# quadbase_ble113.net
KiCad netlist of a schematic drawn in EAGLE
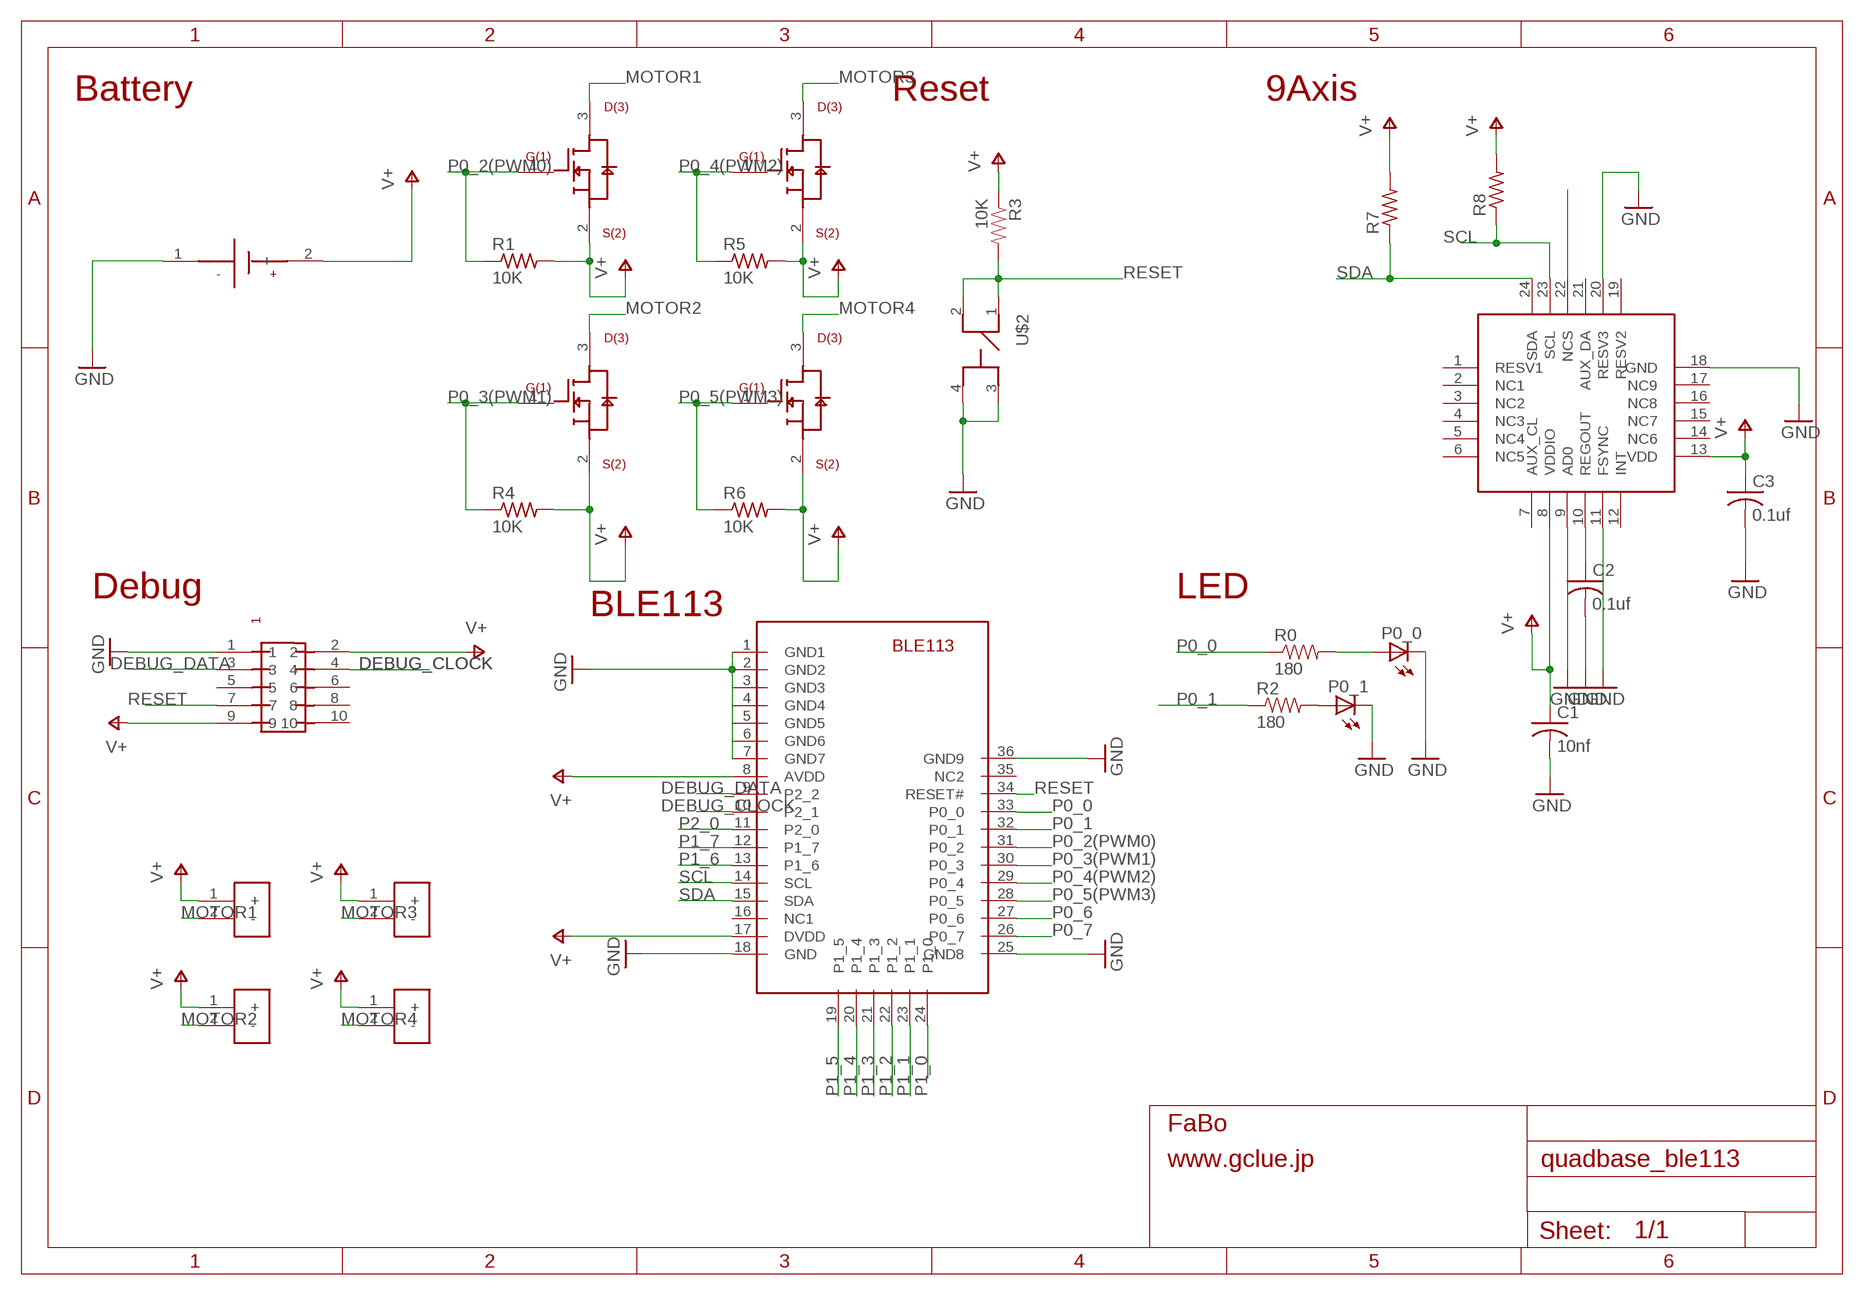
[diagram p0: schematic, sheet 1]

(export (version "E")
  (design (tool "Eeschema 10.0.6"))
  (components
    (comp (ref "C1")
      (value "10nf")
      (footprint "eagle-import:C0603")
      (libsource (lib "eagle-import") (part "C-USC0603"))
    )
    (comp (ref "C2")
      (value "0.1uf")
      (footprint "eagle-import:C0603")
      (libsource (lib "eagle-import") (part "C-USC0603"))
    )
    (comp (ref "C3")
      (value "0.1uf")
      (footprint "eagle-import:C0603")
      (libsource (lib "eagle-import") (part "C-USC0603"))
    )
    (comp (ref "MOTOR1")
      (value "SMD-MOTOR")
      (footprint "eagle-import:SMD-MOTOR")
      (libsource (lib "eagle-import") (part "SMD-MOTOR"))
    )
    (comp (ref "MOTOR2")
      (value "SMD-MOTOR")
      (footprint "eagle-import:SMD-MOTOR")
      (libsource (lib "eagle-import") (part "SMD-MOTOR"))
    )
    (comp (ref "MOTOR3")
      (value "SMD-MOTOR")
      (footprint "eagle-import:SMD-MOTOR")
      (libsource (lib "eagle-import") (part "SMD-MOTOR"))
    )
    (comp (ref "MOTOR4")
      (value "SMD-MOTOR")
      (footprint "eagle-import:SMD-MOTOR")
      (libsource (lib "eagle-import") (part "SMD-MOTOR"))
    )
    (comp (ref "P0_0")
      (value "LEDCHIP-LED0603")
      (footprint "eagle-import:CHIP-LED0603")
      (libsource (lib "eagle-import") (part "LEDCHIP-LED0603"))
    )
    (comp (ref "P0_1")
      (value "LEDCHIP-LED0603")
      (footprint "eagle-import:CHIP-LED0603")
      (libsource (lib "eagle-import") (part "LEDCHIP-LED0603"))
    )
    (comp (ref "R0")
      (value "180")
      (footprint "eagle-import:0603-RES")
      (libsource (lib "eagle-import") (part "RESISTOR0603-RES"))
    )
    (comp (ref "R1")
      (value "10K")
      (footprint "eagle-import:R0603")
      (libsource (lib "eagle-import") (part "R-US_R0603"))
    )
    (comp (ref "R2")
      (value "180")
      (footprint "eagle-import:0603-RES")
      (libsource (lib "eagle-import") (part "RESISTOR0603-RES"))
    )
    (comp (ref "R3")
      (value "10K")
      (footprint "eagle-import:0603-RES")
      (libsource (lib "eagle-import") (part "RESISTOR0603-RES"))
    )
    (comp (ref "R4")
      (value "10K")
      (footprint "eagle-import:R0603")
      (libsource (lib "eagle-import") (part "R-US_R0603"))
    )
    (comp (ref "R5")
      (value "10K")
      (footprint "eagle-import:R0603")
      (libsource (lib "eagle-import") (part "R-US_R0603"))
    )
    (comp (ref "R6")
      (value "10K")
      (footprint "eagle-import:R0603")
      (libsource (lib "eagle-import") (part "R-US_R0603"))
    )
    (comp (ref "R7")
      (value "R-US_R0603")
      (footprint "eagle-import:R0603")
      (libsource (lib "eagle-import") (part "R-US_R0603"))
    )
    (comp (ref "R8")
      (value "R-US_R0603")
      (footprint "eagle-import:R0603")
      (libsource (lib "eagle-import") (part "R-US_R0603"))
    )
    (comp (ref "U$1")
      (value "SMD-SUPPLY")
      (footprint "eagle-import:SMD_SUPPLY")
      (libsource (lib "eagle-import") (part "SMD-SUPPLY"))
    )
    (comp (ref "U$2")
      (value "SWITCH-LS6J2M-T")
      (footprint "eagle-import:SWITCH-LS6J2M-T")
      (libsource (lib "eagle-import") (part "SWITCH-LS6J2M-T"))
    )
    (comp (ref "U$3")
      (value "PIN-HEADER-SMT(1.27MM)2X5")
      (footprint "eagle-import:PIN-HEADER-SMT(1.27MM)2X5")
      (libsource (lib "eagle-import") (part "PIN-HEADER-SMT(1.27MM)2X5"))
    )
    (comp (ref "U$4")
      (value "BLE113")
      (footprint "eagle-import:BLE113")
      (libsource (lib "eagle-import") (part "BLE113"))
    )
    (comp (ref "U$5")
      (value "VISHAY-SI2318CDS")
      (footprint "eagle-import:VISHAY-SI2318CDS")
      (libsource (lib "eagle-import") (part "VISHAY-SI2318CDS"))
    )
    (comp (ref "U$7")
      (value "VISHAY-SI2318CDS")
      (footprint "eagle-import:VISHAY-SI2318CDS")
      (libsource (lib "eagle-import") (part "VISHAY-SI2318CDS"))
    )
    (comp (ref "U$8")
      (value "VISHAY-SI2318CDS")
      (footprint "eagle-import:VISHAY-SI2318CDS")
      (libsource (lib "eagle-import") (part "VISHAY-SI2318CDS"))
    )
    (comp (ref "U$9")
      (value "VISHAY-SI2318CDS")
      (footprint "eagle-import:VISHAY-SI2318CDS")
      (libsource (lib "eagle-import") (part "VISHAY-SI2318CDS"))
    )
    (comp (ref "U$10")
      (value "INVENSENSE-MPU9250")
      (footprint "eagle-import:INVENSENSE-MPU9250")
      (libsource (lib "eagle-import") (part "INVENSENSE-MPU9250"))
    )
  )
  (nets
    (net (code "1") (name "/DEBUG_CLOCK") (class "Default")
      (node (ref "U$3") (pin "4") (pinfunction "4_4") (pintype "bidirectional"))
      (node (ref "U$4") (pin "10") (pinfunction "P2_1_10") (pintype "bidirectional"))
    )
    (net (code "2") (name "/DEBUG_DATA") (class "Default")
      (node (ref "U$3") (pin "3") (pinfunction "3_3") (pintype "bidirectional"))
      (node (ref "U$4") (pin "9") (pinfunction "P2_2_9") (pintype "bidirectional"))
    )
    (net (code "3") (name "/MOTOR1") (class "Default")
      (node (ref "MOTOR1") (pin "2") (pinfunction "-_2") (pintype "bidirectional"))
      (node (ref "U$5") (pin "3") (pinfunction "P$3_3") (pintype "bidirectional"))
    )
    (net (code "4") (name "/MOTOR2") (class "Default")
      (node (ref "MOTOR2") (pin "2") (pinfunction "-_2") (pintype "bidirectional"))
      (node (ref "U$7") (pin "3") (pinfunction "P$3_3") (pintype "bidirectional"))
    )
    (net (code "5") (name "/MOTOR3") (class "Default")
      (node (ref "MOTOR3") (pin "2") (pinfunction "-_2") (pintype "bidirectional"))
      (node (ref "U$8") (pin "3") (pinfunction "P$3_3") (pintype "bidirectional"))
    )
    (net (code "6") (name "/MOTOR4") (class "Default")
      (node (ref "MOTOR4") (pin "2") (pinfunction "-_2") (pintype "bidirectional"))
      (node (ref "U$9") (pin "3") (pinfunction "P$3_3") (pintype "bidirectional"))
    )
    (net (code "7") (name "/P0_0") (class "Default")
      (node (ref "R0") (pin "1") (pinfunction "1_1") (pintype "passive"))
      (node (ref "U$4") (pin "33") (pinfunction "P0_0_33") (pintype "bidirectional"))
    )
    (net (code "8") (name "/P0_1") (class "Default")
      (node (ref "R2") (pin "1") (pinfunction "1_1") (pintype "passive"))
      (node (ref "U$4") (pin "32") (pinfunction "P0_1_32") (pintype "bidirectional"))
    )
    (net (code "9") (name "/P0_2(PWM0)") (class "Default")
      (node (ref "R1") (pin "1") (pinfunction "1_1") (pintype "passive"))
      (node (ref "U$4") (pin "31") (pinfunction "P0_2_31") (pintype "bidirectional"))
      (node (ref "U$5") (pin "1") (pinfunction "P$1_1") (pintype "bidirectional"))
    )
    (net (code "10") (name "/P0_3(PWM1)") (class "Default")
      (node (ref "R4") (pin "1") (pinfunction "1_1") (pintype "passive"))
      (node (ref "U$4") (pin "30") (pinfunction "P0_3_30") (pintype "bidirectional"))
      (node (ref "U$7") (pin "1") (pinfunction "P$1_1") (pintype "bidirectional"))
    )
    (net (code "11") (name "/P0_4(PWM2)") (class "Default")
      (node (ref "R5") (pin "1") (pinfunction "1_1") (pintype "passive"))
      (node (ref "U$4") (pin "29") (pinfunction "P0_4_29") (pintype "bidirectional"))
      (node (ref "U$8") (pin "1") (pinfunction "P$1_1") (pintype "bidirectional"))
    )
    (net (code "12") (name "/P0_5(PWM3)") (class "Default")
      (node (ref "R6") (pin "1") (pinfunction "1_1") (pintype "passive"))
      (node (ref "U$4") (pin "28") (pinfunction "P0_5_28") (pintype "bidirectional"))
      (node (ref "U$9") (pin "1") (pinfunction "P$1_1") (pintype "bidirectional"))
    )
    (net (code "13") (name "/P0_6") (class "Default")
      (node (ref "U$4") (pin "27") (pinfunction "P0_6_27") (pintype "bidirectional"))
    )
    (net (code "14") (name "/P0_7") (class "Default")
      (node (ref "U$4") (pin "26") (pinfunction "P0_7_26") (pintype "bidirectional"))
    )
    (net (code "15") (name "/P1_0") (class "Default")
      (node (ref "U$4") (pin "24") (pinfunction "P1_0_24") (pintype "bidirectional"))
    )
    (net (code "16") (name "/P1_1") (class "Default")
      (node (ref "U$4") (pin "23") (pinfunction "P1_1_23") (pintype "bidirectional"))
    )
    (net (code "17") (name "/P1_2") (class "Default")
      (node (ref "U$4") (pin "22") (pinfunction "P1_2_22") (pintype "bidirectional"))
    )
    (net (code "18") (name "/P1_3") (class "Default")
      (node (ref "U$4") (pin "21") (pinfunction "P1_3_21") (pintype "bidirectional"))
    )
    (net (code "19") (name "/P1_4") (class "Default")
      (node (ref "U$4") (pin "20") (pinfunction "P1_4_20") (pintype "bidirectional"))
    )
    (net (code "20") (name "/P1_5") (class "Default")
      (node (ref "U$4") (pin "19") (pinfunction "P1_5_19") (pintype "bidirectional"))
    )
    (net (code "21") (name "/P1_6") (class "Default")
      (node (ref "U$4") (pin "13") (pinfunction "P1_6_13") (pintype "bidirectional"))
    )
    (net (code "22") (name "/P1_7") (class "Default")
      (node (ref "U$4") (pin "12") (pinfunction "P1_7_12") (pintype "bidirectional"))
    )
    (net (code "23") (name "/P2_0") (class "Default")
      (node (ref "U$4") (pin "11") (pinfunction "P2_0_11") (pintype "bidirectional"))
    )
    (net (code "24") (name "/RESET") (class "Default")
      (node (ref "R3") (pin "2") (pinfunction "2_2") (pintype "passive"))
      (node (ref "U$2") (pin "1") (pinfunction "1_1") (pintype "bidirectional"))
      (node (ref "U$2") (pin "2") (pinfunction "2_2") (pintype "bidirectional"))
      (node (ref "U$3") (pin "7") (pinfunction "7_7") (pintype "bidirectional"))
      (node (ref "U$4") (pin "34") (pinfunction "RESET#_34") (pintype "bidirectional"))
    )
    (net (code "25") (name "/SCL") (class "Default")
      (node (ref "R8") (pin "1") (pinfunction "1_1") (pintype "passive"))
      (node (ref "U$10") (pin "23") (pinfunction "SCL_23") (pintype "bidirectional"))
      (node (ref "U$4") (pin "14") (pinfunction "SCL_14") (pintype "bidirectional"))
    )
    (net (code "26") (name "/SDA") (class "Default")
      (node (ref "R7") (pin "1") (pinfunction "1_1") (pintype "passive"))
      (node (ref "U$10") (pin "24") (pinfunction "SDA_24") (pintype "bidirectional"))
      (node (ref "U$4") (pin "15") (pinfunction "SDA_15") (pintype "bidirectional"))
    )
    (net (code "27") (name "GND") (class "Default")
      (node (ref "C1") (pin "2") (pinfunction "2_2") (pintype "passive"))
      (node (ref "C2") (pin "2") (pinfunction "2_2") (pintype "passive"))
      (node (ref "C3") (pin "2") (pinfunction "2_2") (pintype "passive"))
      (node (ref "P0_0") (pin "C") (pinfunction "C_C") (pintype "passive"))
      (node (ref "P0_1") (pin "C") (pinfunction "C_C") (pintype "passive"))
      (node (ref "U$1") (pin "1") (pinfunction "-_1") (pintype "bidirectional"))
      (node (ref "U$10") (pin "11") (pinfunction "FSYNC_11") (pintype "bidirectional"))
      (node (ref "U$10") (pin "18") (pinfunction "GND_18") (pintype "bidirectional"))
      (node (ref "U$10") (pin "20") (pinfunction "RESV3_20") (pintype "bidirectional"))
      (node (ref "U$10") (pin "9") (pinfunction "AD0_9") (pintype "bidirectional"))
      (node (ref "U$2") (pin "3") (pinfunction "3_3") (pintype "bidirectional"))
      (node (ref "U$2") (pin "4") (pinfunction "4_4") (pintype "bidirectional"))
      (node (ref "U$3") (pin "1") (pinfunction "1_1") (pintype "bidirectional"))
      (node (ref "U$4") (pin "1") (pinfunction "GND1_1") (pintype "bidirectional"))
      (node (ref "U$4") (pin "18") (pinfunction "GND_18") (pintype "bidirectional"))
      (node (ref "U$4") (pin "2") (pinfunction "GND2_2") (pintype "bidirectional"))
      (node (ref "U$4") (pin "25") (pinfunction "GND8_25") (pintype "bidirectional"))
      (node (ref "U$4") (pin "3") (pinfunction "GND3_3") (pintype "bidirectional"))
      (node (ref "U$4") (pin "36") (pinfunction "GND9_36") (pintype "bidirectional"))
      (node (ref "U$4") (pin "4") (pinfunction "GND4_4") (pintype "bidirectional"))
      (node (ref "U$4") (pin "5") (pinfunction "GND5_5") (pintype "bidirectional"))
      (node (ref "U$4") (pin "6") (pinfunction "GND6_6") (pintype "bidirectional"))
      (node (ref "U$4") (pin "7") (pinfunction "GND7_7") (pintype "bidirectional"))
    )
    (net (code "28") (name "Net-(P0_0-PadA)") (class "Default")
      (node (ref "P0_0") (pin "A") (pinfunction "A_A") (pintype "passive"))
      (node (ref "R0") (pin "2") (pinfunction "2_2") (pintype "passive"))
    )
    (net (code "29") (name "Net-(P0_1-PadA)") (class "Default")
      (node (ref "P0_1") (pin "A") (pinfunction "A_A") (pintype "passive"))
      (node (ref "R2") (pin "2") (pinfunction "2_2") (pintype "passive"))
    )
    (net (code "30") (name "Net-(U$10-REGOUT)") (class "Default")
      (node (ref "C2") (pin "1") (pinfunction "1_1") (pintype "passive"))
      (node (ref "U$10") (pin "10") (pinfunction "REGOUT_10") (pintype "bidirectional"))
    )
    (net (code "31") (name "V+") (class "Default")
      (node (ref "C1") (pin "1") (pinfunction "1_1") (pintype "passive"))
      (node (ref "C3") (pin "1") (pinfunction "1_1") (pintype "passive"))
      (node (ref "MOTOR1") (pin "1") (pinfunction "+_1") (pintype "bidirectional"))
      (node (ref "MOTOR2") (pin "1") (pinfunction "+_1") (pintype "bidirectional"))
      (node (ref "MOTOR3") (pin "1") (pinfunction "+_1") (pintype "bidirectional"))
      (node (ref "MOTOR4") (pin "1") (pinfunction "+_1") (pintype "bidirectional"))
      (node (ref "R1") (pin "2") (pinfunction "2_2") (pintype "passive"))
      (node (ref "R3") (pin "1") (pinfunction "1_1") (pintype "passive"))
      (node (ref "R4") (pin "2") (pinfunction "2_2") (pintype "passive"))
      (node (ref "R5") (pin "2") (pinfunction "2_2") (pintype "passive"))
      (node (ref "R6") (pin "2") (pinfunction "2_2") (pintype "passive"))
      (node (ref "R7") (pin "2") (pinfunction "2_2") (pintype "passive"))
      (node (ref "R8") (pin "2") (pinfunction "2_2") (pintype "passive"))
      (node (ref "U$1") (pin "2") (pinfunction "+_2") (pintype "bidirectional"))
      (node (ref "U$10") (pin "13") (pinfunction "VDD_13") (pintype "bidirectional"))
      (node (ref "U$10") (pin "8") (pinfunction "VDDIO_8") (pintype "bidirectional"))
      (node (ref "U$3") (pin "2") (pinfunction "2_2") (pintype "bidirectional"))
      (node (ref "U$3") (pin "9") (pinfunction "9_9") (pintype "bidirectional"))
      (node (ref "U$4") (pin "17") (pinfunction "DVDD_17") (pintype "bidirectional"))
      (node (ref "U$4") (pin "8") (pinfunction "AVDD_8") (pintype "bidirectional"))
      (node (ref "U$5") (pin "2") (pinfunction "P$2_2") (pintype "bidirectional"))
      (node (ref "U$7") (pin "2") (pinfunction "P$2_2") (pintype "bidirectional"))
      (node (ref "U$8") (pin "2") (pinfunction "P$2_2") (pintype "bidirectional"))
      (node (ref "U$9") (pin "2") (pinfunction "P$2_2") (pintype "bidirectional"))
    )
    (net (code "32") (name "unconnected-(U$3-Pad5)") (class "Default")
      (node (ref "U$3") (pin "5") (pinfunction "5_5") (pintype "bidirectional"))
    )
    (net (code "33") (name "unconnected-(U$3-Pad6)") (class "Default")
      (node (ref "U$3") (pin "6") (pinfunction "6_6") (pintype "bidirectional"))
    )
    (net (code "34") (name "unconnected-(U$3-Pad8)") (class "Default")
      (node (ref "U$3") (pin "8") (pinfunction "8_8") (pintype "bidirectional"))
    )
    (net (code "35") (name "unconnected-(U$3-Pad10)") (class "Default")
      (node (ref "U$3") (pin "10") (pinfunction "10_10") (pintype "bidirectional"))
    )
    (net (code "36") (name "unconnected-(U$4-NC1-Pad16)") (class "Default")
      (node (ref "U$4") (pin "16") (pinfunction "NC1_16") (pintype "bidirectional"))
    )
    (net (code "37") (name "unconnected-(U$4-NC2-Pad35)") (class "Default")
      (node (ref "U$4") (pin "35") (pinfunction "NC2_35") (pintype "bidirectional"))
    )
    (net (code "38") (name "unconnected-(U$10-AUX_CL-Pad7)") (class "Default")
      (node (ref "U$10") (pin "7") (pinfunction "AUX_CL_7") (pintype "bidirectional"))
    )
    (net (code "39") (name "unconnected-(U$10-AUX_DA-Pad21)") (class "Default")
      (node (ref "U$10") (pin "21") (pinfunction "AUX_DA_21") (pintype "bidirectional"))
    )
    (net (code "40") (name "unconnected-(U$10-INT-Pad12)") (class "Default")
      (node (ref "U$10") (pin "12") (pinfunction "INT_12") (pintype "bidirectional"))
    )
    (net (code "41") (name "unconnected-(U$10-NC1-Pad2)") (class "Default")
      (node (ref "U$10") (pin "2") (pinfunction "NC1_2") (pintype "bidirectional"))
    )
    (net (code "42") (name "unconnected-(U$10-NC2-Pad3)") (class "Default")
      (node (ref "U$10") (pin "3") (pinfunction "NC2_3") (pintype "bidirectional"))
    )
    (net (code "43") (name "unconnected-(U$10-NC3-Pad4)") (class "Default")
      (node (ref "U$10") (pin "4") (pinfunction "NC3_4") (pintype "bidirectional"))
    )
    (net (code "44") (name "unconnected-(U$10-NC4-Pad5)") (class "Default")
      (node (ref "U$10") (pin "5") (pinfunction "NC4_5") (pintype "bidirectional"))
    )
    (net (code "45") (name "unconnected-(U$10-NC5-Pad6)") (class "Default")
      (node (ref "U$10") (pin "6") (pinfunction "NC5_6") (pintype "bidirectional"))
    )
    (net (code "46") (name "unconnected-(U$10-NC6-Pad14)") (class "Default")
      (node (ref "U$10") (pin "14") (pinfunction "NC6_14") (pintype "bidirectional"))
    )
    (net (code "47") (name "unconnected-(U$10-NC7-Pad15)") (class "Default")
      (node (ref "U$10") (pin "15") (pinfunction "NC7_15") (pintype "bidirectional"))
    )
    (net (code "48") (name "unconnected-(U$10-NC8-Pad16)") (class "Default")
      (node (ref "U$10") (pin "16") (pinfunction "NC8_16") (pintype "bidirectional"))
    )
    (net (code "49") (name "unconnected-(U$10-NC9-Pad17)") (class "Default")
      (node (ref "U$10") (pin "17") (pinfunction "NC9_17") (pintype "bidirectional"))
    )
    (net (code "50") (name "unconnected-(U$10-NCS-Pad22)") (class "Default")
      (node (ref "U$10") (pin "22") (pinfunction "NCS_22") (pintype "bidirectional"))
    )
    (net (code "51") (name "unconnected-(U$10-RESV1-Pad1)") (class "Default")
      (node (ref "U$10") (pin "1") (pinfunction "RESV1_1") (pintype "bidirectional"))
    )
    (net (code "52") (name "unconnected-(U$10-RESV2-Pad19)") (class "Default")
      (node (ref "U$10") (pin "19") (pinfunction "RESV2_19") (pintype "bidirectional"))
    )
  )
)
